# Mircod_TEST_LIST_1.net
KiCad netlist of a schematic drawn in Altium Designer
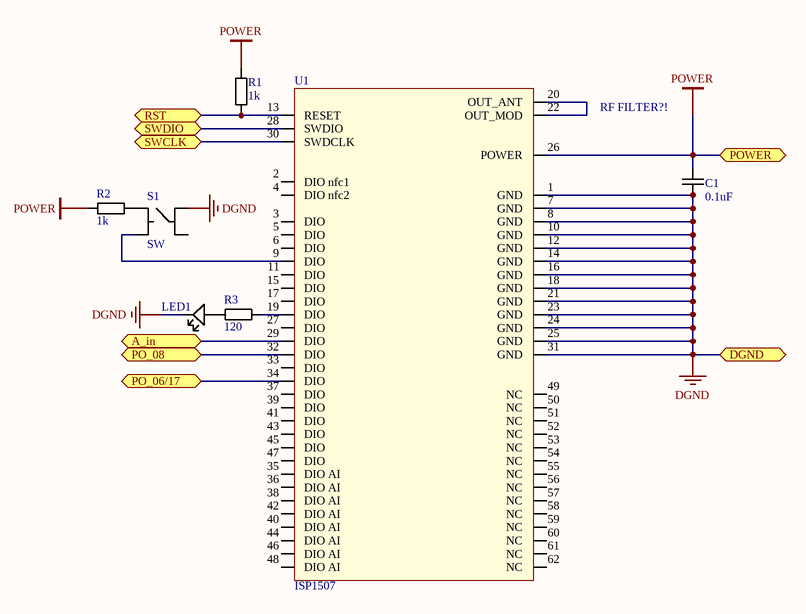
[diagram p0: Mircod_TEST_LIST_1.SchDoc]

(export (version "E")
  (design (tool "Eeschema 10.0.6"))
  (components
    (comp (ref "C1")
      (value "0.1uF")
      (footprint "MIRCOD:Csmd_0402")
      (description "CAPACITOR")
      (libsource (lib "MIRCOD") (part "C_SMD"))
    )
    (comp (ref "LED1") (value "LED") (footprint "MIRCOD:RDSMD_0603") (libsource (lib "MIRCOD") (part "LED")))
    (comp (ref "R1")
      (value "1k")
      (footprint "MIRCOD:SMD_0402")
      (description "RESISTOR")
      (libsource (lib "MIRCOD") (part "R_SMD"))
    )
    (comp (ref "R2")
      (value "1k")
      (footprint "MIRCOD:SMD_0402")
      (description "RESISTOR")
      (libsource (lib "MIRCOD") (part "R_SMD"))
    )
    (comp (ref "R3")
      (value "120")
      (footprint "MIRCOD:SMD_0402")
      (description "RESISTOR")
      (libsource (lib "MIRCOD") (part "R_SMD"))
    )
    (comp (ref "S1")
      (value "SW")
      (footprint "MIRCOD:6x6 Tact Switch")
      (description "KLS7-TS6604 6x6 Tact Switch Series")
      (libsource (lib "MIRCOD") (part "Switch"))
    )
    (comp (ref "U1")
      (value "ISP1507")
      (footprint "MIRCOD:LGA62 ISP1507")
      (description "High Performance Bluetooth 5 Ready, NFC*  & ANT Low Energy Module with MCU & Antenna")
      (libsource (lib "MIRCOD") (part "ISP1507"))
    )
  )
  (nets
    (net (code "1") (name "/A_in") (class "Default")
      (node (ref "U1") (pin "29") (pinfunction "DIO_29") (pintype "passive"))
    )
    (net (code "2") (name "/PO_06{slash}17") (class "Default")
      (node (ref "U1") (pin "34") (pinfunction "DIO_34") (pintype "passive"))
    )
    (net (code "3") (name "/PO_08") (class "Default")
      (node (ref "U1") (pin "32") (pinfunction "DIO_32") (pintype "passive"))
    )
    (net (code "4") (name "/RST") (class "Default")
      (node (ref "R1") (pin "1") (pinfunction "1_1") (pintype "passive"))
      (node (ref "U1") (pin "13") (pinfunction "RESET_13") (pintype "passive"))
    )
    (net (code "5") (name "/SWCLK") (class "Default")
      (node (ref "U1") (pin "30") (pinfunction "SWDCLK_30") (pintype "passive"))
    )
    (net (code "6") (name "/SWDIO") (class "Default")
      (node (ref "U1") (pin "28") (pinfunction "SWDIO_28") (pintype "passive"))
    )
    (net (code "7") (name "DGND") (class "Default")
      (node (ref "C1") (pin "1") (pinfunction "1_1") (pintype "passive"))
      (node (ref "LED1") (pin "2") (pinfunction "2_2") (pintype "passive"))
      (node (ref "S1") (pin "4") (pinfunction "4_4") (pintype "passive"))
      (node (ref "U1") (pin "1") (pinfunction "GND_1") (pintype "passive"))
      (node (ref "U1") (pin "10") (pinfunction "GND_10") (pintype "passive"))
      (node (ref "U1") (pin "12") (pinfunction "GND_12") (pintype "passive"))
      (node (ref "U1") (pin "14") (pinfunction "GND_14") (pintype "passive"))
      (node (ref "U1") (pin "16") (pinfunction "GND_16") (pintype "passive"))
      (node (ref "U1") (pin "18") (pinfunction "GND_18") (pintype "passive"))
      (node (ref "U1") (pin "21") (pinfunction "GND_21") (pintype "passive"))
      (node (ref "U1") (pin "23") (pinfunction "GND_23") (pintype "passive"))
      (node (ref "U1") (pin "24") (pinfunction "GND_24") (pintype "passive"))
      (node (ref "U1") (pin "25") (pinfunction "GND_25") (pintype "passive"))
      (node (ref "U1") (pin "31") (pinfunction "GND_31") (pintype "passive"))
      (node (ref "U1") (pin "7") (pinfunction "GND_7") (pintype "passive"))
      (node (ref "U1") (pin "8") (pinfunction "GND_8") (pintype "passive"))
    )
    (net (code "8") (name "Net-(LED1-Pad1)") (class "Default")
      (node (ref "LED1") (pin "1") (pinfunction "1_1") (pintype "passive"))
      (node (ref "R3") (pin "1") (pinfunction "1_1") (pintype "passive"))
    )
    (net (code "9") (name "Net-(R2-Pad1)") (class "Default")
      (node (ref "R2") (pin "1") (pinfunction "1_1") (pintype "passive"))
      (node (ref "S1") (pin "1") (pinfunction "1_1") (pintype "passive"))
    )
    (net (code "10") (name "Net-(R3-Pad2)") (class "Default")
      (node (ref "R3") (pin "2") (pinfunction "2_2") (pintype "passive"))
      (node (ref "U1") (pin "19") (pinfunction "DIO_19") (pintype "passive"))
    )
    (net (code "11") (name "Net-(S1-Pad2)") (class "Default")
      (node (ref "S1") (pin "2") (pinfunction "2_2") (pintype "passive"))
      (node (ref "U1") (pin "9") (pinfunction "DIO_9") (pintype "passive"))
    )
    (net (code "12") (name "Net-(U1-OUT_ANT)") (class "Default")
      (node (ref "U1") (pin "20") (pinfunction "OUT_ANT_20") (pintype "passive"))
      (node (ref "U1") (pin "22") (pinfunction "OUT_MOD_22") (pintype "passive"))
    )
    (net (code "13") (name "POWER") (class "Default")
      (node (ref "C1") (pin "2") (pinfunction "2_2") (pintype "passive"))
      (node (ref "R1") (pin "2") (pinfunction "2_2") (pintype "passive"))
      (node (ref "R2") (pin "2") (pinfunction "2_2") (pintype "passive"))
      (node (ref "U1") (pin "26") (pinfunction "POWER_26") (pintype "passive"))
    )
    (net (code "14") (name "unconnected-(S1-Pad3)") (class "Default")
      (node (ref "S1") (pin "3") (pinfunction "3_3") (pintype "passive"))
    )
    (net (code "15") (name "unconnected-(U1-DIO-Pad3)") (class "Default")
      (node (ref "U1") (pin "3") (pinfunction "DIO_3") (pintype "passive"))
    )
    (net (code "16") (name "unconnected-(U1-DIO-Pad5)") (class "Default")
      (node (ref "U1") (pin "5") (pinfunction "DIO_5") (pintype "passive"))
    )
    (net (code "17") (name "unconnected-(U1-DIO-Pad6)") (class "Default")
      (node (ref "U1") (pin "6") (pinfunction "DIO_6") (pintype "passive"))
    )
    (net (code "18") (name "unconnected-(U1-DIO-Pad11)") (class "Default")
      (node (ref "U1") (pin "11") (pinfunction "DIO_11") (pintype "passive"))
    )
    (net (code "19") (name "unconnected-(U1-DIO-Pad15)") (class "Default")
      (node (ref "U1") (pin "15") (pinfunction "DIO_15") (pintype "passive"))
    )
    (net (code "20") (name "unconnected-(U1-DIO-Pad17)") (class "Default")
      (node (ref "U1") (pin "17") (pinfunction "DIO_17") (pintype "passive"))
    )
    (net (code "21") (name "unconnected-(U1-DIO-Pad27)") (class "Default")
      (node (ref "U1") (pin "27") (pinfunction "DIO_27") (pintype "passive"))
    )
    (net (code "22") (name "unconnected-(U1-DIO-Pad33)") (class "Default")
      (node (ref "U1") (pin "33") (pinfunction "DIO_33") (pintype "passive"))
    )
    (net (code "23") (name "unconnected-(U1-DIO-Pad37)") (class "Default")
      (node (ref "U1") (pin "37") (pinfunction "DIO_37") (pintype "passive"))
    )
    (net (code "24") (name "unconnected-(U1-DIO-Pad39)") (class "Default")
      (node (ref "U1") (pin "39") (pinfunction "DIO_39") (pintype "passive"))
    )
    (net (code "25") (name "unconnected-(U1-DIO-Pad41)") (class "Default")
      (node (ref "U1") (pin "41") (pinfunction "DIO_41") (pintype "passive"))
    )
    (net (code "26") (name "unconnected-(U1-DIO-Pad43)") (class "Default")
      (node (ref "U1") (pin "43") (pinfunction "DIO_43") (pintype "passive"))
    )
    (net (code "27") (name "unconnected-(U1-DIO-Pad45)") (class "Default")
      (node (ref "U1") (pin "45") (pinfunction "DIO_45") (pintype "passive"))
    )
    (net (code "28") (name "unconnected-(U1-DIO-Pad47)") (class "Default")
      (node (ref "U1") (pin "47") (pinfunction "DIO_47") (pintype "passive"))
    )
    (net (code "29") (name "unconnected-(U1-DIO_AI-Pad35)") (class "Default")
      (node (ref "U1") (pin "35") (pinfunction "DIO_AI_35") (pintype "passive"))
    )
    (net (code "30") (name "unconnected-(U1-DIO_AI-Pad36)") (class "Default")
      (node (ref "U1") (pin "36") (pinfunction "DIO_AI_36") (pintype "passive"))
    )
    (net (code "31") (name "unconnected-(U1-DIO_AI-Pad38)") (class "Default")
      (node (ref "U1") (pin "38") (pinfunction "DIO_AI_38") (pintype "passive"))
    )
    (net (code "32") (name "unconnected-(U1-DIO_AI-Pad40)") (class "Default")
      (node (ref "U1") (pin "40") (pinfunction "DIO_AI_40") (pintype "passive"))
    )
    (net (code "33") (name "unconnected-(U1-DIO_AI-Pad42)") (class "Default")
      (node (ref "U1") (pin "42") (pinfunction "DIO_AI_42") (pintype "passive"))
    )
    (net (code "34") (name "unconnected-(U1-DIO_AI-Pad44)") (class "Default")
      (node (ref "U1") (pin "44") (pinfunction "DIO_AI_44") (pintype "passive"))
    )
    (net (code "35") (name "unconnected-(U1-DIO_AI-Pad46)") (class "Default")
      (node (ref "U1") (pin "46") (pinfunction "DIO_AI_46") (pintype "passive"))
    )
    (net (code "36") (name "unconnected-(U1-DIO_AI-Pad48)") (class "Default")
      (node (ref "U1") (pin "48") (pinfunction "DIO_AI_48") (pintype "passive"))
    )
    (net (code "37") (name "unconnected-(U1-DIO_nfc1-Pad2)") (class "Default")
      (node (ref "U1") (pin "2") (pinfunction "DIO_nfc1_2") (pintype "passive"))
    )
    (net (code "38") (name "unconnected-(U1-DIO_nfc2-Pad4)") (class "Default")
      (node (ref "U1") (pin "4") (pinfunction "DIO_nfc2_4") (pintype "passive"))
    )
    (net (code "39") (name "unconnected-(U1-NC-Pad49)") (class "Default")
      (node (ref "U1") (pin "49") (pinfunction "NC_49") (pintype "passive"))
    )
    (net (code "40") (name "unconnected-(U1-NC-Pad50)") (class "Default")
      (node (ref "U1") (pin "50") (pinfunction "NC_50") (pintype "passive"))
    )
    (net (code "41") (name "unconnected-(U1-NC-Pad51)") (class "Default")
      (node (ref "U1") (pin "51") (pinfunction "NC_51") (pintype "passive"))
    )
    (net (code "42") (name "unconnected-(U1-NC-Pad52)") (class "Default")
      (node (ref "U1") (pin "52") (pinfunction "NC_52") (pintype "passive"))
    )
    (net (code "43") (name "unconnected-(U1-NC-Pad53)") (class "Default")
      (node (ref "U1") (pin "53") (pinfunction "NC_53") (pintype "passive"))
    )
    (net (code "44") (name "unconnected-(U1-NC-Pad54)") (class "Default")
      (node (ref "U1") (pin "54") (pinfunction "NC_54") (pintype "passive"))
    )
    (net (code "45") (name "unconnected-(U1-NC-Pad55)") (class "Default")
      (node (ref "U1") (pin "55") (pinfunction "NC_55") (pintype "passive"))
    )
    (net (code "46") (name "unconnected-(U1-NC-Pad56)") (class "Default")
      (node (ref "U1") (pin "56") (pinfunction "NC_56") (pintype "passive"))
    )
    (net (code "47") (name "unconnected-(U1-NC-Pad57)") (class "Default")
      (node (ref "U1") (pin "57") (pinfunction "NC_57") (pintype "passive"))
    )
    (net (code "48") (name "unconnected-(U1-NC-Pad58)") (class "Default")
      (node (ref "U1") (pin "58") (pinfunction "NC_58") (pintype "passive"))
    )
    (net (code "49") (name "unconnected-(U1-NC-Pad59)") (class "Default")
      (node (ref "U1") (pin "59") (pinfunction "NC_59") (pintype "passive"))
    )
    (net (code "50") (name "unconnected-(U1-NC-Pad60)") (class "Default")
      (node (ref "U1") (pin "60") (pinfunction "NC_60") (pintype "passive"))
    )
    (net (code "51") (name "unconnected-(U1-NC-Pad61)") (class "Default")
      (node (ref "U1") (pin "61") (pinfunction "NC_61") (pintype "passive"))
    )
    (net (code "52") (name "unconnected-(U1-NC-Pad62)") (class "Default")
      (node (ref "U1") (pin "62") (pinfunction "NC_62") (pintype "passive"))
    )
  )
)
